# sim_adapter.net
KiCad netlist of a schematic drawn in EAGLE
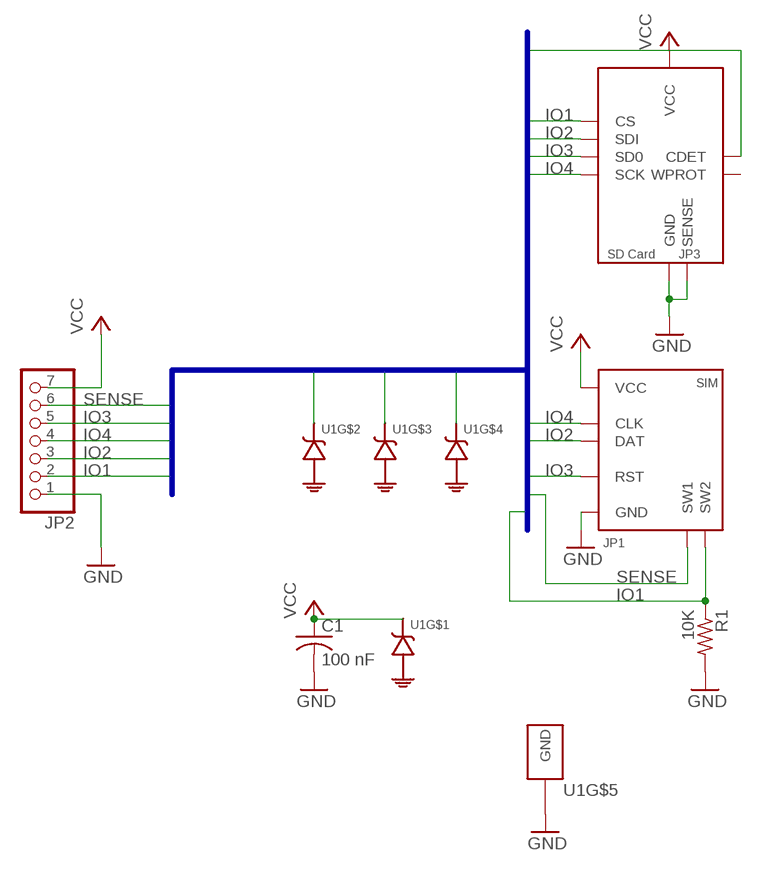
[diagram p0: schematic, sheet 1]

(export (version "E")
  (design (tool "Eeschema 10.0.6"))
  (components
    (comp (ref "C1")
      (value "100 nF")
      (footprint "eagle-import:C0402")
      (libsource (lib "eagle-import") (part "C-USC0402"))
    )
    (comp (ref "JP1")
      (value "SIMHOLDER-8PINHING")
      (footprint "eagle-import:CCM03-SIMHOLDER")
      (libsource (lib "eagle-import") (part "SIMHOLDER-8PINHING"))
    )
    (comp (ref "JP2")
      (value "PINHD-1X7")
      (footprint "eagle-import:1X07")
      (libsource (lib "eagle-import") (part "PINHD-1X7"))
    )
    (comp (ref "JP3")
      (value "SDCARD-HOLDER")
      (footprint "eagle-import:SDHOLDER-9PIN")
      (libsource (lib "eagle-import") (part "SDCARD-HOLDER"))
    )
    (comp (ref "R1")
      (value "10K")
      (footprint "eagle-import:R0603")
      (libsource (lib "eagle-import") (part "R-US_R0603"))
    )
    (comp (ref "U1")
      (value "ESDA6V1SC6")
      (footprint "eagle-import:SOT23-6L")
      (libsource (lib "eagle-import") (part "ESDA6V1SC6"))
    )
  )
  (nets
    (net (code "1") (name "/IO1") (class "Default")
      (node (ref "JP1") (pin "SW2") (pinfunction "SW2_SW2") (pintype "bidirectional"))
      (node (ref "JP2") (pin "2") (pinfunction "2_2") (pintype "passive"))
      (node (ref "JP3") (pin "1") (pinfunction "CS_1") (pintype "bidirectional"))
      (node (ref "R1") (pin "1") (pinfunction "1_1") (pintype "passive"))
    )
    (net (code "2") (name "/IO2") (class "Default")
      (node (ref "JP1") (pin "IO") (pinfunction "DAT_IO") (pintype "bidirectional"))
      (node (ref "JP2") (pin "3") (pinfunction "3_3") (pintype "passive"))
      (node (ref "JP3") (pin "2") (pinfunction "SDI_2") (pintype "bidirectional"))
      (node (ref "U1") (pin "3") (pinfunction "P$1_3") (pintype "input"))
    )
    (net (code "3") (name "/IO3") (class "Default")
      (node (ref "JP1") (pin "RESET") (pinfunction "RST_RESET") (pintype "bidirectional"))
      (node (ref "JP2") (pin "5") (pinfunction "5_5") (pintype "passive"))
      (node (ref "JP3") (pin "7") (pinfunction "SD0_7") (pintype "bidirectional"))
      (node (ref "U1") (pin "4") (pinfunction "P$1_4") (pintype "input"))
    )
    (net (code "4") (name "/IO4") (class "Default")
      (node (ref "JP1") (pin "CLOCK") (pinfunction "CLK_CLOCK") (pintype "bidirectional"))
      (node (ref "JP2") (pin "4") (pinfunction "4_4") (pintype "passive"))
      (node (ref "JP3") (pin "5") (pinfunction "SCK_5") (pintype "bidirectional"))
      (node (ref "U1") (pin "6") (pinfunction "P$1_6") (pintype "input"))
    )
    (net (code "5") (name "/SENSE") (class "Default")
      (node (ref "JP1") (pin "SW1") (pinfunction "SW1_SW1") (pintype "bidirectional"))
      (node (ref "JP2") (pin "6") (pinfunction "6_6") (pintype "passive"))
      (node (ref "JP3") (pin "CDETECT") (pinfunction "CDET_CDETECT") (pintype "bidirectional"))
    )
    (net (code "6") (name "GND") (class "Default")
      (node (ref "C1") (pin "2") (pinfunction "2_2") (pintype "passive"))
      (node (ref "JP1") (pin "GND") (pinfunction "GND_GND") (pintype "bidirectional"))
      (node (ref "JP2") (pin "1") (pinfunction "1_1") (pintype "passive"))
      (node (ref "JP3") (pin "3") (pinfunction "GND_3") (pintype "bidirectional"))
      (node (ref "JP3") (pin "6") (pinfunction "GND_6") (pintype "bidirectional"))
      (node (ref "JP3") (pin "CDGND") (pinfunction "SENSE_CDGND") (pintype "bidirectional"))
      (node (ref "JP3") (pin "CDGND_BOT") (pinfunction "SENSE_CDGND_BOT") (pintype "bidirectional"))
      (node (ref "JP3") (pin "WPGND") (pinfunction "SENSE_WPGND") (pintype "bidirectional"))
      (node (ref "JP3") (pin "WPGND_BOT") (pinfunction "SENSE_WPGND_BOT") (pintype "bidirectional"))
      (node (ref "R1") (pin "2") (pinfunction "2_2") (pintype "passive"))
      (node (ref "U1") (pin "2") (pinfunction "GND_2") (pintype "power_in"))
      (node (ref "U1") (pin "5") (pinfunction "GND_5") (pintype "power_in"))
    )
    (net (code "7") (name "VCC") (class "Default")
      (node (ref "C1") (pin "1") (pinfunction "1_1") (pintype "passive"))
      (node (ref "JP1") (pin "VCC") (pinfunction "VCC_VCC") (pintype "bidirectional"))
      (node (ref "JP2") (pin "7") (pinfunction "7_7") (pintype "passive"))
      (node (ref "JP3") (pin "4") (pinfunction "VCC_4") (pintype "bidirectional"))
      (node (ref "U1") (pin "1") (pinfunction "P$1_1") (pintype "input"))
    )
    (net (code "8") (name "unconnected-(JP3-WPROT-PadWPROTECT)") (class "Default")
      (node (ref "JP3") (pin "WPROTECT") (pinfunction "WPROT_WPROTECT") (pintype "bidirectional"))
    )
  )
)
